# 3_-MCU_MAIN.net
KiCad netlist of a schematic drawn in Altium Designer
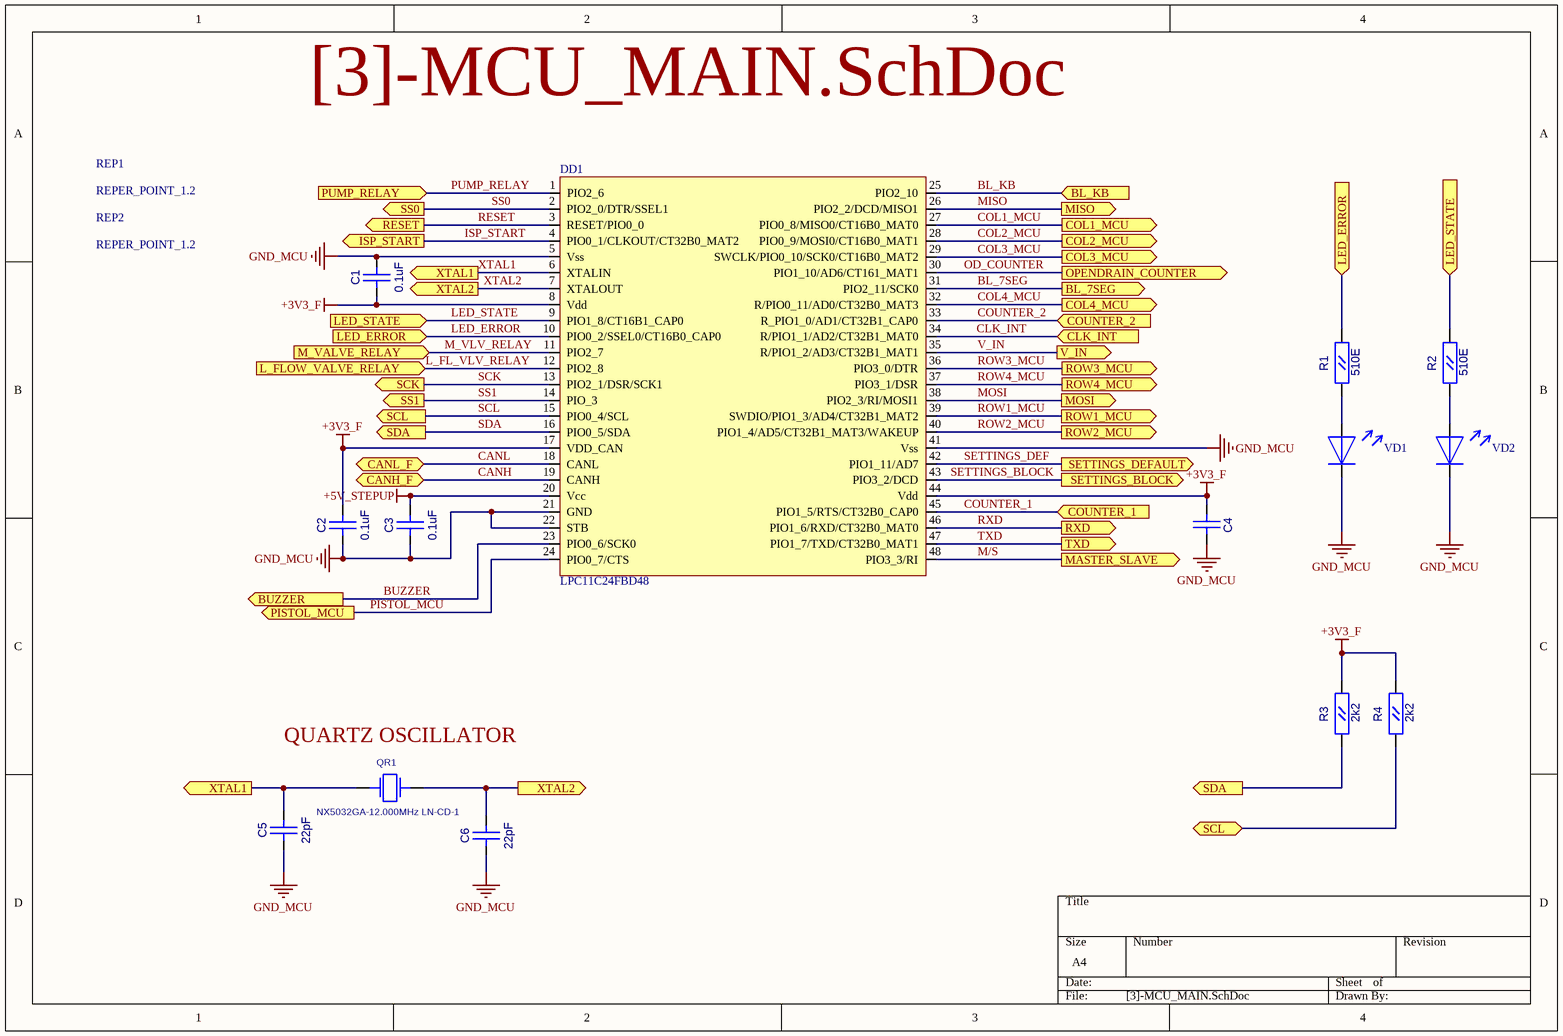
[diagram p0: [3]-MCU_MAIN.SchDoc]

(export (version "E")
  (design (tool "Eeschema 10.0.6"))
  (components
    (comp (ref "C1")
      (value "0.1uF")
      (footprint "CC0603")
      (description "CC0603")
      (libsource (lib "gprs_modem_2") (part "CC0603"))
    )
    (comp (ref "C2")
      (value "0.1uF")
      (footprint "CC0603")
      (description "CC0603")
      (libsource (lib "gprs_modem_2") (part "CC0603"))
    )
    (comp (ref "C3")
      (value "0.1uF")
      (footprint "CC0603")
      (description "CC0603")
      (libsource (lib "gprs_modem_2") (part "CC0603"))
    )
    (comp (ref "C4")
      (value "~")
      (footprint "CC0603")
      (description "CC0603")
      (libsource (lib "fizik_lib") (part "CC0603"))
    )
    (comp (ref "C5")
      (value "22pF")
      (footprint "CC0603")
      (description "CC0603")
      (libsource (lib "gprs_modem_2") (part "CC0603"))
    )
    (comp (ref "C6")
      (value "22pF")
      (footprint "CC0603")
      (description "CC0603")
      (libsource (lib "gprs_modem_2") (part "CC0603"))
    )
    (comp (ref "DD1")
      (value "LPC11C24FBD48")
      (footprint "LQFP48")
      (libsource (lib "fizik_lib") (part "LPC11C24FBD48"))
    )
    (comp (ref "QR1")
      (value "NX5032GA-12.000MHz LN-CD-1")
      (footprint "AC5032_2")
      (description "AC5032/2")
      (libsource (lib "gprs_modem_2") (part "AC5032_2"))
    )
    (comp (ref "R1")
      (value "510E")
      (footprint "RC0603")
      (description "RC0603")
      (libsource (lib "fizik_lib") (part "RC0603"))
    )
    (comp (ref "R2")
      (value "510E")
      (footprint "RC0603")
      (description "RC0603")
      (libsource (lib "fizik_lib") (part "RC0603"))
    )
    (comp (ref "R3")
      (value "2k2")
      (footprint "RC0603")
      (description "RC0603")
      (libsource (lib "fizik_lib") (part "RC0603"))
    )
    (comp (ref "R4")
      (value "2k2")
      (footprint "RC0603")
      (description "RC0603")
      (libsource (lib "fizik_lib") (part "RC0603"))
    )
    (comp (ref "REP1")
      (value "REPER_POINT_1.2")
      (footprint "REPER1.2")
      (description "REPER1.2")
      (libsource (lib "fizik_lib") (part "REPER1.2"))
    )
    (comp (ref "REP2")
      (value "REPER_POINT_1.2")
      (footprint "REPER1.2")
      (description "REPER1.2")
      (libsource (lib "fizik_lib") (part "REPER1.2"))
    )
    (comp (ref "VD1")
      (value "LED_0805")
      (footprint "LED0805")
      (libsource (lib "fizik_lib") (part "LED_0805"))
    )
    (comp (ref "VD2")
      (value "LED_0805")
      (footprint "LED0805")
      (libsource (lib "fizik_lib") (part "LED_0805"))
    )
  )
  (nets
    (net (code "1") (name "+3V3_F") (class "Default")
      (node (ref "C1") (pin "1") (pinfunction "A_1") (pintype "passive"))
      (node (ref "C2") (pin "2") (pinfunction "B_2") (pintype "passive"))
      (node (ref "C4") (pin "1") (pinfunction "A_1") (pintype "passive"))
      (node (ref "DD1") (pin "17") (pinfunction "VDD_CAN_17") (pintype "passive"))
      (node (ref "DD1") (pin "44") (pinfunction "Vdd_44") (pintype "passive"))
      (node (ref "DD1") (pin "8") (pinfunction "Vdd_8") (pintype "passive"))
      (node (ref "R3") (pin "2") (pinfunction "B_2") (pintype "passive"))
      (node (ref "R4") (pin "2") (pinfunction "B_2") (pintype "passive"))
    )
    (net (code "2") (name "+5V_STEPUP") (class "Default")
      (node (ref "C3") (pin "2") (pinfunction "B_2") (pintype "passive"))
      (node (ref "DD1") (pin "20") (pinfunction "Vcc_20") (pintype "passive"))
    )
    (net (code "3") (name "/BL_7SEG") (class "Default")
      (node (ref "DD1") (pin "31") (pinfunction "PIO2_11/SCK0_31") (pintype "passive"))
    )
    (net (code "4") (name "/BL_KB") (class "Default")
      (node (ref "DD1") (pin "25") (pinfunction "PIO2_10_25") (pintype "passive"))
    )
    (net (code "5") (name "/BUZZER") (class "Default")
      (node (ref "DD1") (pin "23") (pinfunction "PIO0_6/SCK0_23") (pintype "passive"))
    )
    (net (code "6") (name "/CANH") (class "Default")
      (node (ref "DD1") (pin "19") (pinfunction "CANH_19") (pintype "passive"))
    )
    (net (code "7") (name "/CANL") (class "Default")
      (node (ref "DD1") (pin "18") (pinfunction "CANL_18") (pintype "passive"))
    )
    (net (code "8") (name "/CLK_INT") (class "Default")
      (node (ref "DD1") (pin "34") (pinfunction "R/PIO1_1/AD2/CT32B1_MAT0_34") (pintype "passive"))
    )
    (net (code "9") (name "/COL1_MCU") (class "Default")
      (node (ref "DD1") (pin "27") (pinfunction "PIO0_8/MISO0/CT16B0_MAT0_27") (pintype "passive"))
    )
    (net (code "10") (name "/COL2_MCU") (class "Default")
      (node (ref "DD1") (pin "28") (pinfunction "PIO0_9/MOSI0/CT16B0_MAT1_28") (pintype "passive"))
    )
    (net (code "11") (name "/COL3_MCU") (class "Default")
      (node (ref "DD1") (pin "29") (pinfunction "SWCLK/PIO0_10/SCK0/CT16B0_MAT2_29") (pintype "passive"))
    )
    (net (code "12") (name "/COL4_MCU") (class "Default")
      (node (ref "DD1") (pin "32") (pinfunction "R/PIO0_11/AD0/CT32B0_MAT3_32") (pintype "passive"))
    )
    (net (code "13") (name "/COUNTER_1") (class "Default")
      (node (ref "DD1") (pin "45") (pinfunction "PIO1_5/RTS/CT32B0_CAP0_45") (pintype "passive"))
    )
    (net (code "14") (name "/COUNTER_2") (class "Default")
      (node (ref "DD1") (pin "33") (pinfunction "R_PIO1_0/AD1/CT32B1_CAP0_33") (pintype "passive"))
    )
    (net (code "15") (name "/ISP_START") (class "Default")
      (node (ref "DD1") (pin "4") (pinfunction "PIO0_1/CLKOUT/CT32B0_MAT2_4") (pintype "passive"))
    )
    (net (code "16") (name "/LED_ERROR") (class "Default")
      (node (ref "DD1") (pin "10") (pinfunction "PIO0_2/SSEL0/CT16B0_CAP0_10") (pintype "passive"))
      (node (ref "R1") (pin "2") (pinfunction "B_2") (pintype "passive"))
    )
    (net (code "17") (name "/LED_STATE") (class "Default")
      (node (ref "DD1") (pin "9") (pinfunction "PIO1_8/CT16B1_CAP0_9") (pintype "passive"))
      (node (ref "R2") (pin "2") (pinfunction "B_2") (pintype "passive"))
    )
    (net (code "18") (name "/L_FL_VLV_RELAY") (class "Default")
      (node (ref "DD1") (pin "12") (pinfunction "PIO2_8_12") (pintype "passive"))
    )
    (net (code "19") (name "/MISO") (class "Default")
      (node (ref "DD1") (pin "26") (pinfunction "PIO2_2/DCD/MISO1_26") (pintype "passive"))
    )
    (net (code "20") (name "/MOSI") (class "Default")
      (node (ref "DD1") (pin "38") (pinfunction "PIO2_3/RI/MOSI1_38") (pintype "passive"))
    )
    (net (code "21") (name "/M_VLV_RELAY") (class "Default")
      (node (ref "DD1") (pin "11") (pinfunction "PIO2_7_11") (pintype "passive"))
    )
    (net (code "22") (name "/M{slash}S") (class "Default")
      (node (ref "DD1") (pin "48") (pinfunction "PIO3_3/RI_48") (pintype "passive"))
    )
    (net (code "23") (name "/OD_COUNTER") (class "Default")
      (node (ref "DD1") (pin "30") (pinfunction "PIO1_10/AD6/CT161_MAT1_30") (pintype "passive"))
    )
    (net (code "24") (name "/PISTOL_MCU") (class "Default")
      (node (ref "DD1") (pin "24") (pinfunction "PIO0_7/CTS_24") (pintype "passive"))
    )
    (net (code "25") (name "/PUMP_RELAY") (class "Default")
      (node (ref "DD1") (pin "1") (pinfunction "PIO2_6_1") (pintype "passive"))
    )
    (net (code "26") (name "/RESET") (class "Default")
      (node (ref "DD1") (pin "3") (pinfunction "RESET/PIO0_0_3") (pintype "passive"))
    )
    (net (code "27") (name "/ROW1_MCU") (class "Default")
      (node (ref "DD1") (pin "39") (pinfunction "SWDIO/PIO1_3/AD4/CT32B1_MAT2_39") (pintype "passive"))
    )
    (net (code "28") (name "/ROW2_MCU") (class "Default")
      (node (ref "DD1") (pin "40") (pinfunction "PIO1_4/AD5/CT32B1_MAT3/WAKEUP_40") (pintype "passive"))
    )
    (net (code "29") (name "/ROW3_MCU") (class "Default")
      (node (ref "DD1") (pin "36") (pinfunction "PIO3_0/DTR_36") (pintype "passive"))
    )
    (net (code "30") (name "/ROW4_MCU") (class "Default")
      (node (ref "DD1") (pin "37") (pinfunction "PIO3_1/DSR_37") (pintype "passive"))
    )
    (net (code "31") (name "/RXD") (class "Default")
      (node (ref "DD1") (pin "46") (pinfunction "PIO1_6/RXD/CT32B0_MAT0_46") (pintype "passive"))
    )
    (net (code "32") (name "/SCK") (class "Default")
      (node (ref "DD1") (pin "13") (pinfunction "PIO2_1/DSR/SCK1_13") (pintype "passive"))
    )
    (net (code "33") (name "/SCL") (class "Default")
      (node (ref "DD1") (pin "15") (pinfunction "PIO0_4/SCL_15") (pintype "passive"))
      (node (ref "R4") (pin "1") (pinfunction "A_1") (pintype "passive"))
    )
    (net (code "34") (name "/SDA") (class "Default")
      (node (ref "DD1") (pin "16") (pinfunction "PIO0_5/SDA_16") (pintype "passive"))
      (node (ref "R3") (pin "1") (pinfunction "A_1") (pintype "passive"))
    )
    (net (code "35") (name "/SETTINGS_BLOCK") (class "Default")
      (node (ref "DD1") (pin "43") (pinfunction "PIO3_2/DCD_43") (pintype "passive"))
    )
    (net (code "36") (name "/SETTINGS_DEF") (class "Default")
      (node (ref "DD1") (pin "42") (pinfunction "PIO1_11/AD7_42") (pintype "passive"))
    )
    (net (code "37") (name "/SS0") (class "Default")
      (node (ref "DD1") (pin "2") (pinfunction "PIO2_0/DTR/SSEL1_2") (pintype "passive"))
    )
    (net (code "38") (name "/SS1") (class "Default")
      (node (ref "DD1") (pin "14") (pinfunction "PIO_3_14") (pintype "passive"))
    )
    (net (code "39") (name "/TXD") (class "Default")
      (node (ref "DD1") (pin "47") (pinfunction "PIO1_7/TXD/CT32B0_MAT1_47") (pintype "passive"))
    )
    (net (code "40") (name "/V_IN") (class "Default")
      (node (ref "DD1") (pin "35") (pinfunction "R/PIO1_2/AD3/CT32B1_MAT1_35") (pintype "passive"))
    )
    (net (code "41") (name "/XTAL1") (class "Default")
      (node (ref "C5") (pin "2") (pinfunction "B_2") (pintype "passive"))
      (node (ref "DD1") (pin "6") (pinfunction "XTALIN_6") (pintype "passive"))
      (node (ref "QR1") (pin "1") (pintype "passive"))
    )
    (net (code "42") (name "/XTAL2") (class "Default")
      (node (ref "C6") (pin "2") (pinfunction "B_2") (pintype "passive"))
      (node (ref "DD1") (pin "7") (pinfunction "XTALOUT_7") (pintype "passive"))
      (node (ref "QR1") (pin "2") (pintype "passive"))
    )
    (net (code "43") (name "GND_MCU") (class "Default")
      (node (ref "C1") (pin "2") (pinfunction "B_2") (pintype "passive"))
      (node (ref "C2") (pin "1") (pinfunction "A_1") (pintype "passive"))
      (node (ref "C3") (pin "1") (pinfunction "A_1") (pintype "passive"))
      (node (ref "C4") (pin "2") (pinfunction "B_2") (pintype "passive"))
      (node (ref "C5") (pin "1") (pinfunction "A_1") (pintype "passive"))
      (node (ref "C6") (pin "1") (pinfunction "A_1") (pintype "passive"))
      (node (ref "DD1") (pin "21") (pinfunction "GND_21") (pintype "passive"))
      (node (ref "DD1") (pin "22") (pinfunction "STB_22") (pintype "passive"))
      (node (ref "DD1") (pin "41") (pinfunction "Vss_41") (pintype "passive"))
      (node (ref "DD1") (pin "5") (pinfunction "Vss_5") (pintype "passive"))
      (node (ref "VD1") (pin "2") (pintype "passive"))
      (node (ref "VD2") (pin "2") (pintype "passive"))
    )
    (net (code "44") (name "Net-(R1-A)") (class "Default")
      (node (ref "R1") (pin "1") (pinfunction "A_1") (pintype "passive"))
      (node (ref "VD1") (pin "1") (pintype "passive"))
    )
    (net (code "45") (name "Net-(R2-A)") (class "Default")
      (node (ref "R2") (pin "1") (pinfunction "A_1") (pintype "passive"))
      (node (ref "VD2") (pin "1") (pintype "passive"))
    )
    (net (code "46") (name "unconnected-(REP1-Pad1)") (class "Default")
      (node (ref "REP1") (pin "1") (pintype "passive"))
    )
    (net (code "47") (name "unconnected-(REP2-Pad1)") (class "Default")
      (node (ref "REP2") (pin "1") (pintype "passive"))
    )
  )
)
